# High_Current_H-Bridge.net
KiCad netlist of a schematic drawn in Altium Designer
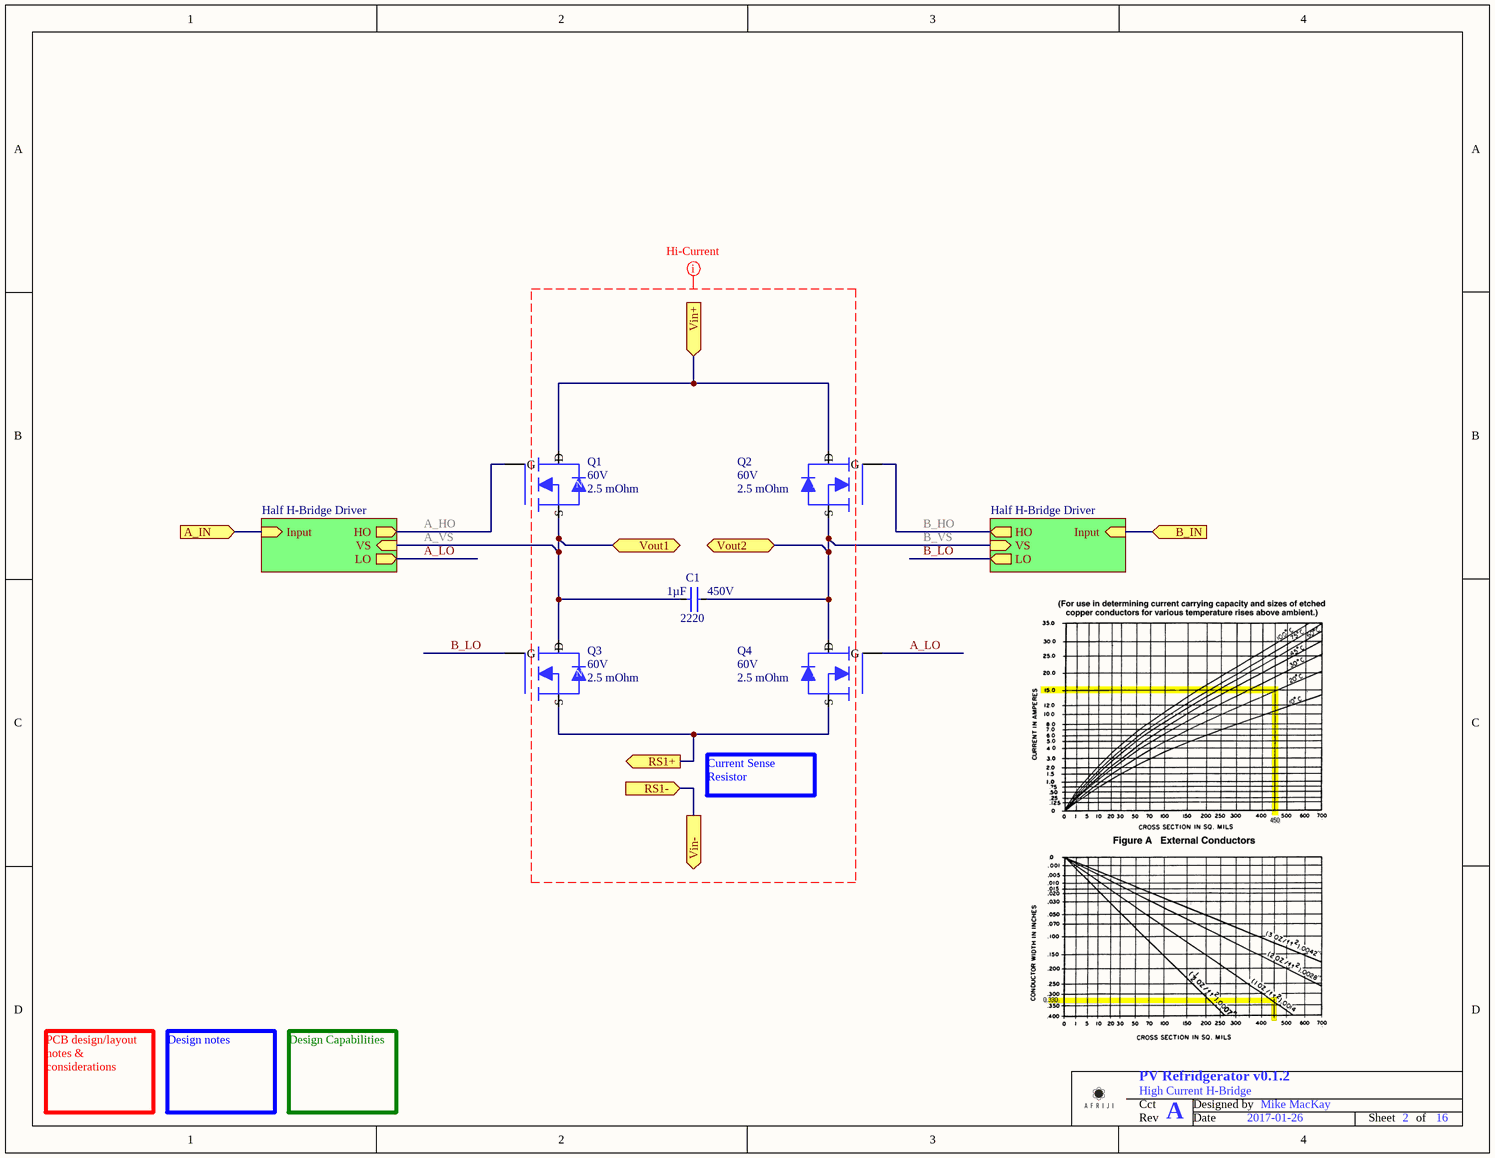
[diagram p0: High Current H-Bridge.SchDoc]

(export (version "E")
  (design (tool "Eeschema 10.0.6"))
  (components
    (comp (ref "C1")
      (value "1uF 2220 450V")
      (footprint "C2220 - Ceramic")
      (fields
        (field (name "MANUFACTURER") "TDK Corporation")
        (field (name "MANUFACTURER PART NUMBER") "CGA9P4X7T2W105M250KE")
        (field (name "TOLERANCE") "±20%")
        (field (name "CAPACITANCE") "1µF")
        (field (name "VOLTAGE - RATED") "450V")
        (field (name "PACKAGE / CASE") "2220")
      )
      (libsource (lib "Local Library") (part "1uF 2220 450V"))
    )
    (comp (ref "Q1")
      (value "N-MOSFET")
      (footprint "DPAK")
      (fields
        (field (name "MANUFACTURER") "Infineon Technologies")
        (field (name "MANUFACTURER PART NUMBER") "IPD025N06N")
        (field (name "DRAIN TO SOURCE VOLTAGE (VDSS)") "60V")
        (field (name "RDS ON (MAX) @ ID, VGS") "2.5 mOhm")
      )
      (libsource (lib "Local Library") (part "N-MOSFET 2.5mR 60V"))
    )
    (comp (ref "Q2")
      (value "N-MOSFET")
      (footprint "DPAK")
      (fields
        (field (name "MANUFACTURER") "Infineon Technologies")
        (field (name "MANUFACTURER PART NUMBER") "IPD025N06N")
        (field (name "DRAIN TO SOURCE VOLTAGE (VDSS)") "60V")
        (field (name "RDS ON (MAX) @ ID, VGS") "2.5 mOhm")
      )
      (libsource (lib "Local Library") (part "N-MOSFET 2.5mR 60V"))
    )
    (comp (ref "Q3")
      (value "N-MOSFET")
      (footprint "DPAK")
      (fields
        (field (name "MANUFACTURER") "Infineon Technologies")
        (field (name "MANUFACTURER PART NUMBER") "IPD025N06N")
        (field (name "DRAIN TO SOURCE VOLTAGE (VDSS)") "60V")
        (field (name "RDS ON (MAX) @ ID, VGS") "2.5 mOhm")
      )
      (libsource (lib "Local Library") (part "N-MOSFET 2.5mR 60V"))
    )
    (comp (ref "Q4")
      (value "N-MOSFET")
      (footprint "DPAK")
      (fields
        (field (name "MANUFACTURER") "Infineon Technologies")
        (field (name "MANUFACTURER PART NUMBER") "IPD025N06N")
        (field (name "DRAIN TO SOURCE VOLTAGE (VDSS)") "60V")
        (field (name "RDS ON (MAX) @ ID, VGS") "2.5 mOhm")
      )
      (libsource (lib "Local Library") (part "N-MOSFET 2.5mR 60V"))
    )
  )
  (nets
    (net (code "1") (name "/A_HO") (class "Default")
      (node (ref "Q1") (pin "1") (pinfunction "G_1") (pintype "passive"))
    )
    (net (code "3") (name "/A_LO") (class "Default")
      (node (ref "Q4") (pin "1") (pinfunction "G_1") (pintype "passive"))
    )
    (net (code "4") (name "/A_VS") (class "Default")
      (node (ref "C1") (pin "1") (pinfunction "1_1") (pintype "passive"))
      (node (ref "Q1") (pin "3") (pinfunction "S_3") (pintype "passive"))
      (node (ref "Q3") (pin "2") (pinfunction "D_2") (pintype "passive"))
    )
    (net (code "5") (name "/B_HO") (class "Default")
      (node (ref "Q2") (pin "1") (pinfunction "G_1") (pintype "passive"))
    )
    (net (code "7") (name "/B_LO") (class "Default")
      (node (ref "Q3") (pin "1") (pinfunction "G_1") (pintype "passive"))
    )
    (net (code "8") (name "/B_VS") (class "Default")
      (node (ref "C1") (pin "2") (pinfunction "2_2") (pintype "passive"))
      (node (ref "Q2") (pin "3") (pinfunction "S_3") (pintype "passive"))
      (node (ref "Q4") (pin "2") (pinfunction "D_2") (pintype "passive"))
    )
    (net (code "9") (name "/RS1+") (class "Default")
      (node (ref "Q3") (pin "3") (pinfunction "S_3") (pintype "passive"))
      (node (ref "Q4") (pin "3") (pinfunction "S_3") (pintype "passive"))
    )
    (net (code "11") (name "/Vin+") (class "Default")
      (node (ref "Q1") (pin "2") (pinfunction "D_2") (pintype "passive"))
      (node (ref "Q2") (pin "2") (pinfunction "D_2") (pintype "passive"))
    )
  )
)
